# SINTETIZADOR_Y_MEZCLADOR.net
KiCad netlist of a schematic drawn in Altium Designer
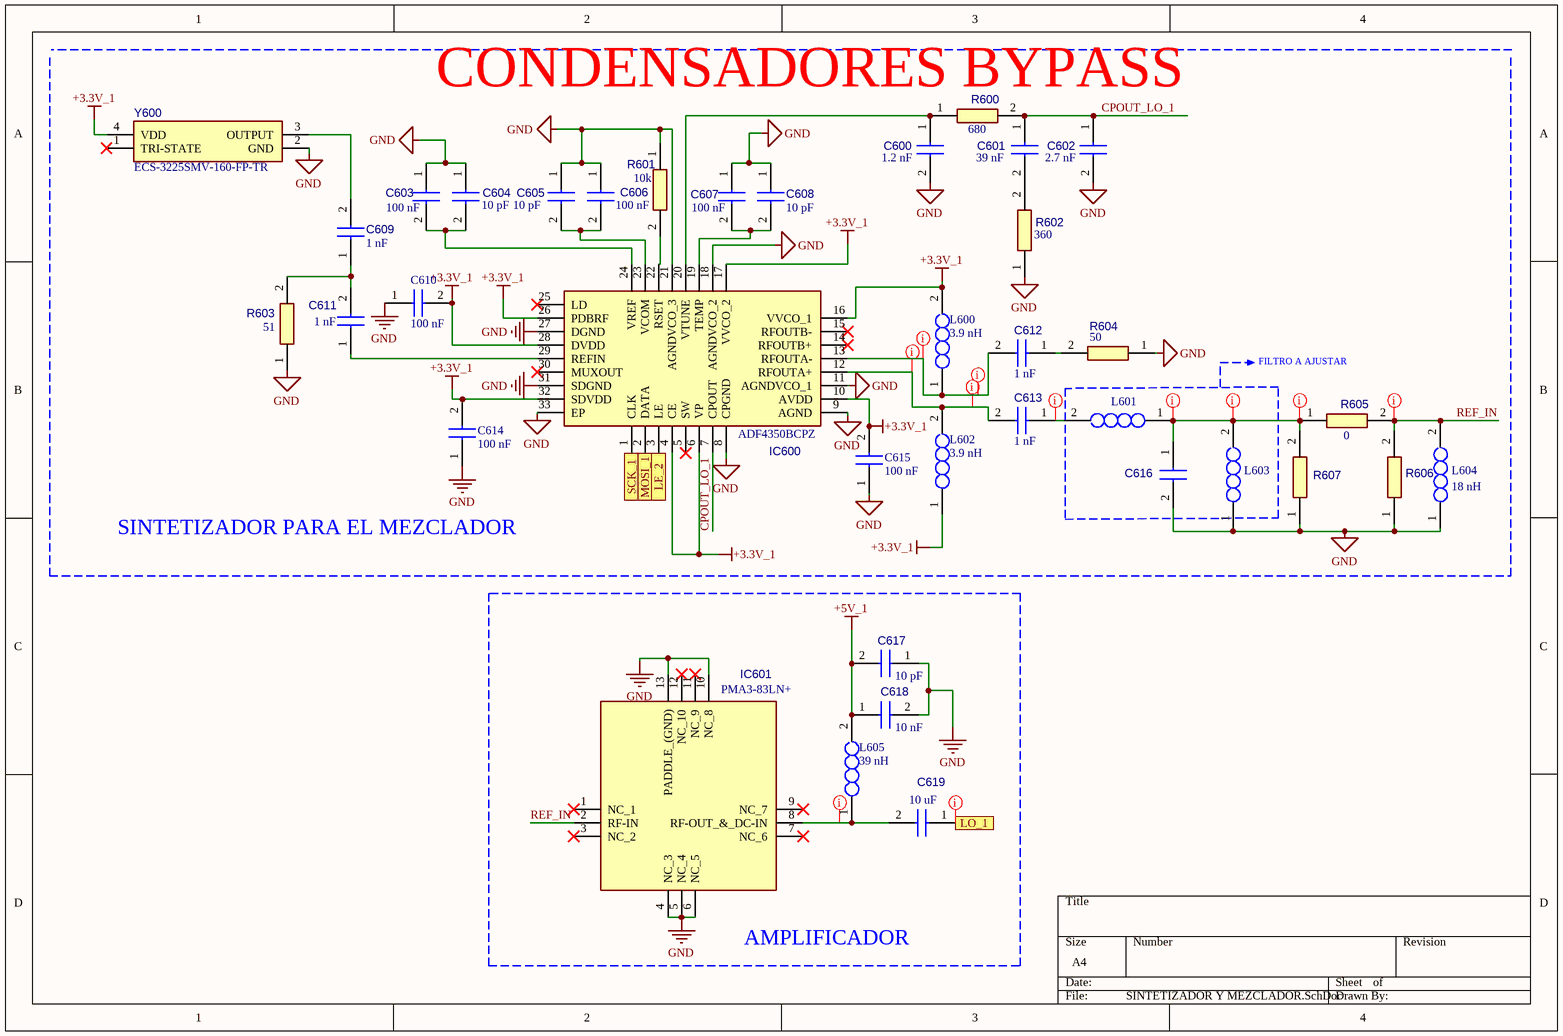
[diagram p0: SINTETIZADOR Y MEZCLADOR.SchDoc]

(export (version "E")
  (design (tool "Eeschema 10.0.6"))
  (components
    (comp (ref "C600")
      (value "1.2 nF")
      (footprint "SamacSys:C0603")
      (description "Capacitor")
      (fields (field (name "MANUFACTURER_PART_NUMBER") "C0603H470J5GACTU"))
      (libsource (lib "*") (part "C0603H470J5GACTU"))
    )
    (comp (ref "C601")
      (value "39 nF")
      (footprint "SamacSys:C0603")
      (description "Capacitor")
      (fields (field (name "MANUFACTURER_PART_NUMBER") "C0603H470J5GACTU"))
      (libsource (lib "*") (part "C0603H470J5GACTU"))
    )
    (comp (ref "C602")
      (value "2.7 nF")
      (footprint "SamacSys:C0603")
      (description "Capacitor")
      (fields (field (name "MANUFACTURER_PART_NUMBER") "C0603H470J5GACTU"))
      (libsource (lib "*") (part "C0603H470J5GACTU"))
    )
    (comp (ref "C603")
      (value "100 nF")
      (footprint "SamacSys:C0603")
      (description "Capacitor")
      (fields (field (name "MANUFACTURER_PART_NUMBER") "C0603H470J5GACTU"))
      (libsource (lib "*") (part "C0603H470J5GACTU"))
    )
    (comp (ref "C604")
      (value "10 pF")
      (footprint "SamacSys:C0603")
      (description "Capacitor")
      (fields (field (name "MANUFACTURER_PART_NUMBER") "C0603H470J5GACTU"))
      (libsource (lib "*") (part "C0603H470J5GACTU"))
    )
    (comp (ref "C605")
      (value "10 pF")
      (footprint "SamacSys:C0603")
      (description "Capacitor")
      (fields (field (name "MANUFACTURER_PART_NUMBER") "C0603H470J5GACTU"))
      (libsource (lib "*") (part "C0603H470J5GACTU"))
    )
    (comp (ref "C606")
      (value "100 nF")
      (footprint "SamacSys:C0603")
      (description "Capacitor")
      (fields (field (name "MANUFACTURER_PART_NUMBER") "C0603H470J5GACTU"))
      (libsource (lib "*") (part "C0603H470J5GACTU"))
    )
    (comp (ref "C607")
      (value "100 nF")
      (footprint "SamacSys:C0603")
      (description "Capacitor")
      (fields (field (name "MANUFACTURER_PART_NUMBER") "C0603H470J5GACTU"))
      (libsource (lib "*") (part "C0603H470J5GACTU"))
    )
    (comp (ref "C608")
      (value "10 pF")
      (footprint "SamacSys:C0603")
      (description "Capacitor")
      (fields (field (name "MANUFACTURER_PART_NUMBER") "C0603H470J5GACTU"))
      (libsource (lib "*") (part "C0603H470J5GACTU"))
    )
    (comp (ref "C609")
      (value "1 nF")
      (footprint "SamacSys:C0603")
      (description "Capacitor")
      (fields (field (name "MANUFACTURER_PART_NUMBER") "C0603H470J5GACTU"))
      (libsource (lib "*") (part "C0603H470J5GACTU"))
    )
    (comp (ref "C610")
      (value "100 nF")
      (footprint "SamacSys:C0603")
      (description "Capacitor")
      (fields (field (name "MANUFACTURER_PART_NUMBER") "C0603H470J5GACTU"))
      (libsource (lib "LIBRERIA_GEN_V2.0") (part "C0603H470J5GACTU"))
    )
    (comp (ref "C611")
      (value "1 nF")
      (footprint "SamacSys:C0603")
      (description "Capacitor")
      (fields (field (name "MANUFACTURER_PART_NUMBER") "C0603H470J5GACTU"))
      (libsource (lib "*") (part "C0603H470J5GACTU"))
    )
    (comp (ref "C612")
      (value "1 nF")
      (footprint "SamacSys:C0603")
      (description "Capacitor")
      (fields (field (name "MANUFACTURER_PART_NUMBER") "C0603H470J5GACTU"))
      (libsource (lib "*") (part "C0603H470J5GACTU"))
    )
    (comp (ref "C613")
      (value "1 nF")
      (footprint "SamacSys:C0603")
      (description "Capacitor")
      (fields (field (name "MANUFACTURER_PART_NUMBER") "C0603H470J5GACTU"))
      (libsource (lib "*") (part "C0603H470J5GACTU"))
    )
    (comp (ref "C614")
      (value "100 nF")
      (footprint "SamacSys:C0603")
      (description "Capacitor")
      (fields (field (name "MANUFACTURER_PART_NUMBER") "C0603H470J5GACTU"))
      (libsource (lib "LIBRERIA_GEN_V2.0") (part "C0603H470J5GACTU"))
    )
    (comp (ref "C615")
      (value "100 nF")
      (footprint "SamacSys:C0603")
      (description "Capacitor")
      (fields (field (name "MANUFACTURER_PART_NUMBER") "C0603H470J5GACTU"))
      (libsource (lib "LIBRERIA_GEN_V2.0") (part "C0603H470J5GACTU"))
    )
    (comp (ref "C616")
      (value "FILTRO")
      (footprint "SamacSys:C0603")
      (description "Capacitor")
      (fields (field (name "MANUFACTURER_PART_NUMBER") "C0603H470J5GACTU"))
      (libsource (lib "*") (part "C0603H470J5GACTU"))
    )
    (comp (ref "C617")
      (value "10 pF")
      (footprint "SamacSys:C0603")
      (description "Capacitor")
      (fields (field (name "MANUFACTURER_PART_NUMBER") "C0603H470J5GACTU"))
      (libsource (lib "*") (part "C0603H470J5GACTU"))
    )
    (comp (ref "C618")
      (value "10 nF")
      (footprint "SamacSys:C0603")
      (description "Capacitor")
      (fields (field (name "MANUFACTURER_PART_NUMBER") "C0603H470J5GACTU"))
      (libsource (lib "*") (part "C0603H470J5GACTU"))
    )
    (comp (ref "C619")
      (value "10 uF")
      (footprint "SamacSys:C0603")
      (description "Capacitor")
      (fields (field (name "MANUFACTURER_PART_NUMBER") "C0603H470J5GACTU"))
      (libsource (lib "*") (part "C0603H470J5GACTU"))
    )
    (comp (ref "IC600")
      (value "ADF4350BCPZ")
      (footprint "SamacSys:QFN50P500X500X100-33N")
      (description "Integrated Circuit")
      (fields (field (name "MOUSER PART NUMBER") "584-ADF4350BCPZ"))
      (libsource (lib "*") (part "ADF4350BCPZ"))
    )
    (comp (ref "IC601")
      (value "PMA3-83LN+")
      (footprint "SamacSys:QFN51P300X300X89-13N")
      (description "Integrated Circuit")
      (fields (field (name "MOUSER PART NUMBER") "139-PMA3-83LN"))
      (libsource (lib "*") (part "PMA3-83LN+"))
    )
    (comp (ref "L600")
      (value "3.9 nH")
      (footprint "SamacSys:INDC1608X95N")
      (description "Inductor")
      (fields
        (field (name "MANUFACTURER_PART_NUMBER") "AIML-0603-100K-T")
        (field (name "MOUSER PART NUMBER") "815-AIML-0603-100KT")
      )
      (libsource (lib "*") (part "AIML-0603-100K-T"))
    )
    (comp (ref "L601")
      (value "3.9 nH")
      (footprint "SamacSys:INDC1608X95N")
      (description "Inductor")
      (fields
        (field (name "MANUFACTURER_PART_NUMBER") "AIML-0603-100K-T")
        (field (name "MOUSER PART NUMBER") "815-AIML-0603-100KT")
      )
      (libsource (lib "*") (part "AIML-0603-100K-T"))
    )
    (comp (ref "L602")
      (value "3.9 nH")
      (footprint "SamacSys:INDC1608X95N")
      (description "Inductor")
      (fields
        (field (name "MANUFACTURER_PART_NUMBER") "AIML-0603-100K-T")
        (field (name "MOUSER PART NUMBER") "815-AIML-0603-100KT")
      )
      (libsource (lib "*") (part "AIML-0603-100K-T"))
    )
    (comp (ref "L603")
      (value "3.9 nH")
      (footprint "SamacSys:INDC1608X95N")
      (description "Inductor")
      (fields
        (field (name "MANUFACTURER_PART_NUMBER") "AIML-0603-100K-T")
        (field (name "MOUSER PART NUMBER") "815-AIML-0603-100KT")
      )
      (libsource (lib "*") (part "AIML-0603-100K-T"))
    )
    (comp (ref "L604")
      (value "18 nH")
      (footprint "SamacSys:INDC1608X95N")
      (description "Inductor")
      (fields
        (field (name "MANUFACTURER_PART_NUMBER") "AIML-0603-100K-T")
        (field (name "MOUSER PART NUMBER") "815-AIML-0603-100KT")
      )
      (libsource (lib "*") (part "AIML-0603-100K-T"))
    )
    (comp (ref "L605")
      (value "39 nH")
      (footprint "SamacSys:INDC1608X95N")
      (description "Inductor")
      (fields
        (field (name "MANUFACTURER_PART_NUMBER") "AIML-0603-100K-T")
        (field (name "MOUSER PART NUMBER") "815-AIML-0603-100KT")
      )
      (libsource (lib "*") (part "AIML-0603-100K-T"))
    )
    (comp (ref "R600")
      (value "680")
      (footprint "SamacSys:RESC1608X55N")
      (description "Resistor")
      (fields
        (field (name "MANUFACTURER_PART_NUMBER") "CR0603-FX-1431ELF")
        (field (name "MOUSER PART NUMBER") "652-CR0603FX-1431ELF")
      )
      (libsource (lib "") (part "CR0603-FX-1431ELF_1"))
    )
    (comp (ref "R601")
      (value "10k")
      (footprint "SamacSys:RESC1608X55N")
      (description "Resistor")
      (fields
        (field (name "MANUFACTURER_PART_NUMBER") "CR0603-FX-1431ELF")
        (field (name "MOUSER PART NUMBER") "652-CR0603FX-1431ELF")
      )
      (libsource (lib "") (part "CR0603-FX-1431ELF_3"))
    )
    (comp (ref "R602")
      (value "360")
      (footprint "SamacSys:RESC1608X55N")
      (description "Resistor")
      (fields
        (field (name "MANUFACTURER_PART_NUMBER") "CR0603-FX-1431ELF")
        (field (name "MOUSER PART NUMBER") "652-CR0603FX-1431ELF")
      )
      (libsource (lib "*") (part "CR0603-FX-1431ELF"))
    )
    (comp (ref "R603")
      (value "51")
      (footprint "SamacSys:RESC1608X55N")
      (description "Resistor")
      (fields
        (field (name "MANUFACTURER_PART_NUMBER") "CR0603-FX-1431ELF")
        (field (name "MOUSER PART NUMBER") "652-CR0603FX-1431ELF")
      )
      (libsource (lib "*") (part "CR0603-FX-1431ELF"))
    )
    (comp (ref "R604")
      (value "50")
      (footprint "SamacSys:RESC1608X55N")
      (description "Resistor")
      (fields
        (field (name "MANUFACTURER_PART_NUMBER") "CR0603-FX-1431ELF")
        (field (name "MOUSER PART NUMBER") "652-CR0603FX-1431ELF")
      )
      (libsource (lib "") (part "CR0603-FX-1431ELF_2"))
    )
    (comp (ref "R605")
      (value "0")
      (footprint "SamacSys:RESC1608X55N")
      (description "Resistor")
      (fields
        (field (name "MANUFACTURER_PART_NUMBER") "CR0603-FX-1431ELF")
        (field (name "MOUSER PART NUMBER") "652-CR0603FX-1431ELF")
      )
      (libsource (lib "") (part "CR0603-FX-1431ELF_1"))
    )
    (comp (ref "R606")
      (value "68")
      (footprint "SamacSys:RESC1608X55N")
      (description "Resistor")
      (fields
        (field (name "MANUFACTURER_PART_NUMBER") "CR0603-FX-1431ELF")
        (field (name "MOUSER PART NUMBER") "652-CR0603FX-1431ELF")
      )
      (libsource (lib "*") (part "CR0603-FX-1431ELF"))
    )
    (comp (ref "R607")
      (value "68")
      (footprint "SamacSys:RESC1608X55N")
      (description "Resistor")
      (fields
        (field (name "MANUFACTURER_PART_NUMBER") "CR0603-FX-1431ELF")
        (field (name "MOUSER PART NUMBER") "652-CR0603FX-1431ELF")
      )
      (libsource (lib "*") (part "CR0603-FX-1431ELF"))
    )
    (comp (ref "Y600")
      (value "ECS-3225SMV-160-FP-TR")
      (footprint "SamacSys:ECS3225SMV160FPTR")
      (description "Crystal or Oscillator")
      (fields (field (name "MOUSER PART NUMBER") "520-3225SMV-160-FPT"))
      (libsource (lib "*") (part "ECS-3225SMV-160-FP-TR"))
    )
  )
  (nets
    (net (code "1") (name "+3.3V_1") (class "Default")
      (node (ref "C610") (pin "2") (pinfunction "2_2") (pintype "passive"))
      (node (ref "C614") (pin "2") (pinfunction "2_2") (pintype "passive"))
      (node (ref "C615") (pin "2") (pinfunction "2_2") (pintype "passive"))
      (node (ref "IC600") (pin "10") (pinfunction "AVDD_10") (pintype "passive"))
      (node (ref "IC600") (pin "16") (pinfunction "VVCO_1_16") (pintype "passive"))
      (node (ref "IC600") (pin "17") (pinfunction "VVCO_2_17") (pintype "passive"))
      (node (ref "IC600") (pin "26") (pinfunction "PDBRF_26") (pintype "passive"))
      (node (ref "IC600") (pin "28") (pinfunction "DVDD_28") (pintype "passive"))
      (node (ref "IC600") (pin "32") (pinfunction "SDVDD_32") (pintype "passive"))
      (node (ref "IC600") (pin "4") (pinfunction "CE_4") (pintype "passive"))
      (node (ref "IC600") (pin "6") (pinfunction "VP_6") (pintype "passive"))
      (node (ref "L600") (pin "2") (pinfunction "2_2") (pintype "passive"))
      (node (ref "L602") (pin "1") (pinfunction "1_1") (pintype "passive"))
      (node (ref "Y600") (pin "4") (pinfunction "VDD_4") (pintype "passive"))
    )
    (net (code "2") (name "+5V_1") (class "Default")
      (node (ref "C617") (pin "2") (pinfunction "2_2") (pintype "passive"))
      (node (ref "C618") (pin "1") (pinfunction "1_1") (pintype "passive"))
      (node (ref "L605") (pin "2") (pinfunction "2_2") (pintype "passive"))
    )
    (net (code "3") (name "/CPOUT_LO_1") (class "Default")
      (node (ref "C601") (pin "1") (pinfunction "1_1") (pintype "passive"))
      (node (ref "C602") (pin "1") (pinfunction "1_1") (pintype "passive"))
      (node (ref "IC600") (pin "7") (pinfunction "CPOUT_7") (pintype "passive"))
      (node (ref "R600") (pin "2") (pinfunction "2_2") (pintype "passive"))
    )
    (net (code "4") (name "/LE_2") (class "Default")
      (node (ref "IC600") (pin "3") (pinfunction "LE_3") (pintype "passive"))
    )
    (net (code "5") (name "/LO_1") (class "Default")
      (node (ref "C619") (pin "1") (pinfunction "1_1") (pintype "passive"))
    )
    (net (code "6") (name "/MOSI_1") (class "Default")
      (node (ref "IC600") (pin "2") (pinfunction "DATA_2") (pintype "passive"))
    )
    (net (code "7") (name "/REF_IN") (class "Default")
      (node (ref "IC601") (pin "2") (pinfunction "RF-IN_2") (pintype "passive"))
      (node (ref "L604") (pin "2") (pinfunction "2_2") (pintype "passive"))
      (node (ref "R605") (pin "2") (pinfunction "2_2") (pintype "passive"))
      (node (ref "R606") (pin "2") (pinfunction "2_2") (pintype "passive"))
    )
    (net (code "8") (name "/SCK_1") (class "Default")
      (node (ref "IC600") (pin "1") (pinfunction "CLK_1") (pintype "passive"))
    )
    (net (code "9") (name "GND") (class "Default")
      (node (ref "C600") (pin "2") (pinfunction "2_2") (pintype "passive"))
      (node (ref "C602") (pin "2") (pinfunction "2_2") (pintype "passive"))
      (node (ref "C603") (pin "1") (pinfunction "1_1") (pintype "passive"))
      (node (ref "C604") (pin "1") (pinfunction "1_1") (pintype "passive"))
      (node (ref "C605") (pin "1") (pinfunction "1_1") (pintype "passive"))
      (node (ref "C606") (pin "1") (pinfunction "1_1") (pintype "passive"))
      (node (ref "C607") (pin "1") (pinfunction "1_1") (pintype "passive"))
      (node (ref "C608") (pin "1") (pinfunction "1_1") (pintype "passive"))
      (node (ref "C610") (pin "1") (pinfunction "1_1") (pintype "passive"))
      (node (ref "C614") (pin "1") (pinfunction "1_1") (pintype "passive"))
      (node (ref "C615") (pin "1") (pinfunction "1_1") (pintype "passive"))
      (node (ref "C616") (pin "2") (pinfunction "2_2") (pintype "passive"))
      (node (ref "C617") (pin "1") (pinfunction "1_1") (pintype "passive"))
      (node (ref "C618") (pin "2") (pinfunction "2_2") (pintype "passive"))
      (node (ref "IC600") (pin "11") (pinfunction "AGNDVCO_1_11") (pintype "passive"))
      (node (ref "IC600") (pin "18") (pinfunction "AGNDVCO_2_18") (pintype "passive"))
      (node (ref "IC600") (pin "21") (pinfunction "AGNDVCO_3_21") (pintype "passive"))
      (node (ref "IC600") (pin "27") (pinfunction "DGND_27") (pintype "passive"))
      (node (ref "IC600") (pin "31") (pinfunction "SDGND_31") (pintype "passive"))
      (node (ref "IC600") (pin "33") (pinfunction "EP_33") (pintype "passive"))
      (node (ref "IC600") (pin "8") (pinfunction "CPGND_8") (pintype "passive"))
      (node (ref "IC600") (pin "9") (pinfunction "AGND_9") (pintype "passive"))
      (node (ref "IC601") (pin "10") (pinfunction "NC_8_10") (pintype "passive"))
      (node (ref "IC601") (pin "13") (pinfunction "PADDLE_(GND)_13") (pintype "passive"))
      (node (ref "IC601") (pin "4") (pinfunction "NC_3_4") (pintype "passive"))
      (node (ref "IC601") (pin "5") (pinfunction "NC_4_5") (pintype "passive"))
      (node (ref "IC601") (pin "6") (pinfunction "NC_5_6") (pintype "passive"))
      (node (ref "L603") (pin "1") (pinfunction "1_1") (pintype "passive"))
      (node (ref "L604") (pin "1") (pinfunction "1_1") (pintype "passive"))
      (node (ref "R601") (pin "1") (pinfunction "1_1") (pintype "passive"))
      (node (ref "R602") (pin "1") (pinfunction "1_1") (pintype "passive"))
      (node (ref "R603") (pin "1") (pinfunction "1_1") (pintype "passive"))
      (node (ref "R604") (pin "1") (pinfunction "1_1") (pintype "passive"))
      (node (ref "R606") (pin "1") (pinfunction "1_1") (pintype "passive"))
      (node (ref "R607") (pin "1") (pinfunction "1_1") (pintype "passive"))
      (node (ref "Y600") (pin "2") (pinfunction "GND_2") (pintype "passive"))
    )
    (net (code "10") (name "Net-(C601-Pad2)") (class "Default")
      (node (ref "C601") (pin "2") (pinfunction "2_2") (pintype "passive"))
      (node (ref "R602") (pin "2") (pinfunction "2_2") (pintype "passive"))
    )
    (net (code "11") (name "Net-(C609-Pad1)") (class "Default")
      (node (ref "C609") (pin "1") (pinfunction "1_1") (pintype "passive"))
      (node (ref "C611") (pin "2") (pinfunction "2_2") (pintype "passive"))
      (node (ref "R603") (pin "2") (pinfunction "2_2") (pintype "passive"))
    )
    (net (code "12") (name "Net-(C612-Pad1)") (class "Default")
      (node (ref "C612") (pin "1") (pinfunction "1_1") (pintype "passive"))
      (node (ref "R604") (pin "2") (pinfunction "2_2") (pintype "passive"))
    )
    (net (code "13") (name "Net-(C613-Pad1)") (class "Default")
      (node (ref "C613") (pin "1") (pinfunction "1_1") (pintype "passive"))
      (node (ref "L601") (pin "2") (pinfunction "2_2") (pintype "passive"))
    )
    (net (code "14") (name "Net-(C616-Pad1)") (class "Default")
      (node (ref "C616") (pin "1") (pinfunction "1_1") (pintype "passive"))
      (node (ref "L601") (pin "1") (pinfunction "1_1") (pintype "passive"))
      (node (ref "L603") (pin "2") (pinfunction "2_2") (pintype "passive"))
      (node (ref "R605") (pin "1") (pinfunction "1_1") (pintype "passive"))
      (node (ref "R607") (pin "2") (pinfunction "2_2") (pintype "passive"))
    )
    (net (code "15") (name "Net-(IC600-REFIN)") (class "Default")
      (node (ref "C611") (pin "1") (pinfunction "1_1") (pintype "passive"))
      (node (ref "IC600") (pin "29") (pinfunction "REFIN_29") (pintype "passive"))
    )
    (net (code "16") (name "Net-(IC600-RFOUTA+)") (class "Default")
      (node (ref "C613") (pin "2") (pinfunction "2_2") (pintype "passive"))
      (node (ref "IC600") (pin "12") (pinfunction "RFOUTA+_12") (pintype "passive"))
      (node (ref "L602") (pin "2") (pinfunction "2_2") (pintype "passive"))
    )
    (net (code "17") (name "Net-(IC600-RFOUTA-)") (class "Default")
      (node (ref "C612") (pin "2") (pinfunction "2_2") (pintype "passive"))
      (node (ref "IC600") (pin "13") (pinfunction "RFOUTA-_13") (pintype "passive"))
      (node (ref "L600") (pin "1") (pinfunction "1_1") (pintype "passive"))
    )
    (net (code "18") (name "Net-(IC600-RSET)") (class "Default")
      (node (ref "IC600") (pin "22") (pinfunction "RSET_22") (pintype "passive"))
      (node (ref "R601") (pin "2") (pinfunction "2_2") (pintype "passive"))
    )
    (net (code "19") (name "Net-(IC600-TEMP)") (class "Default")
      (node (ref "C607") (pin "2") (pinfunction "2_2") (pintype "passive"))
      (node (ref "C608") (pin "2") (pinfunction "2_2") (pintype "passive"))
      (node (ref "IC600") (pin "19") (pinfunction "TEMP_19") (pintype "passive"))
    )
    (net (code "20") (name "Net-(IC600-VCOM)") (class "Default")
      (node (ref "C605") (pin "2") (pinfunction "2_2") (pintype "passive"))
      (node (ref "C606") (pin "2") (pinfunction "2_2") (pintype "passive"))
      (node (ref "IC600") (pin "23") (pinfunction "VCOM_23") (pintype "passive"))
    )
    (net (code "21") (name "Net-(IC600-VREF)") (class "Default")
      (node (ref "C603") (pin "2") (pinfunction "2_2") (pintype "passive"))
      (node (ref "C604") (pin "2") (pinfunction "2_2") (pintype "passive"))
      (node (ref "IC600") (pin "24") (pinfunction "VREF_24") (pintype "passive"))
    )
    (net (code "22") (name "Net-(IC600-VTUNE)") (class "Default")
      (node (ref "C600") (pin "1") (pinfunction "1_1") (pintype "passive"))
      (node (ref "IC600") (pin "20") (pinfunction "VTUNE_20") (pintype "passive"))
      (node (ref "R600") (pin "1") (pinfunction "1_1") (pintype "passive"))
    )
    (net (code "23") (name "Net-(IC601-RF-OUT_&_DC-IN)") (class "Default")
      (node (ref "C619") (pin "2") (pinfunction "2_2") (pintype "passive"))
      (node (ref "IC601") (pin "8") (pinfunction "RF-OUT_&_DC-IN_8") (pintype "passive"))
      (node (ref "L605") (pin "1") (pinfunction "1_1") (pintype "passive"))
    )
    (net (code "24") (name "Net-(Y600-OUTPUT)") (class "Default")
      (node (ref "C609") (pin "2") (pinfunction "2_2") (pintype "passive"))
      (node (ref "Y600") (pin "3") (pinfunction "OUTPUT_3") (pintype "passive"))
    )
    (net (code "25") (name "unconnected-(IC600-LD-Pad25)") (class "Default")
      (node (ref "IC600") (pin "25") (pinfunction "LD_25") (pintype "passive+no_connect"))
    )
    (net (code "26") (name "unconnected-(IC600-MUXOUT-Pad30)") (class "Default")
      (node (ref "IC600") (pin "30") (pinfunction "MUXOUT_30") (pintype "passive+no_connect"))
    )
    (net (code "27") (name "unconnected-(IC600-RFOUTB+-Pad14)") (class "Default")
      (node (ref "IC600") (pin "14") (pinfunction "RFOUTB+_14") (pintype "passive+no_connect"))
    )
    (net (code "28") (name "unconnected-(IC600-RFOUTB--Pad15)") (class "Default")
      (node (ref "IC600") (pin "15") (pinfunction "RFOUTB-_15") (pintype "passive+no_connect"))
    )
    (net (code "29") (name "unconnected-(IC600-SW-Pad5)") (class "Default")
      (node (ref "IC600") (pin "5") (pinfunction "SW_5") (pintype "passive+no_connect"))
    )
    (net (code "30") (name "unconnected-(IC601-NC_1-Pad1)") (class "Default")
      (node (ref "IC601") (pin "1") (pinfunction "NC_1_1") (pintype "passive+no_connect"))
    )
    (net (code "31") (name "unconnected-(IC601-NC_2-Pad3)") (class "Default")
      (node (ref "IC601") (pin "3") (pinfunction "NC_2_3") (pintype "passive+no_connect"))
    )
    (net (code "32") (name "unconnected-(IC601-NC_6-Pad7)") (class "Default")
      (node (ref "IC601") (pin "7") (pinfunction "NC_6_7") (pintype "passive+no_connect"))
    )
    (net (code "33") (name "unconnected-(IC601-NC_7-Pad9)") (class "Default")
      (node (ref "IC601") (pin "9") (pinfunction "NC_7_9") (pintype "passive+no_connect"))
    )
    (net (code "34") (name "unconnected-(IC601-NC_9-Pad11)") (class "Default")
      (node (ref "IC601") (pin "11") (pinfunction "NC_9_11") (pintype "passive+no_connect"))
    )
    (net (code "35") (name "unconnected-(IC601-NC_10-Pad12)") (class "Default")
      (node (ref "IC601") (pin "12") (pinfunction "NC_10_12") (pintype "passive+no_connect"))
    )
    (net (code "36") (name "unconnected-(Y600-TRI-STATE-Pad1)") (class "Default")
      (node (ref "Y600") (pin "1") (pinfunction "TRI-STATE_1") (pintype "passive+no_connect"))
    )
  )
)
